# SCH_MEGO_Node_V1.net
KiCad netlist of a schematic drawn in Altium Designer
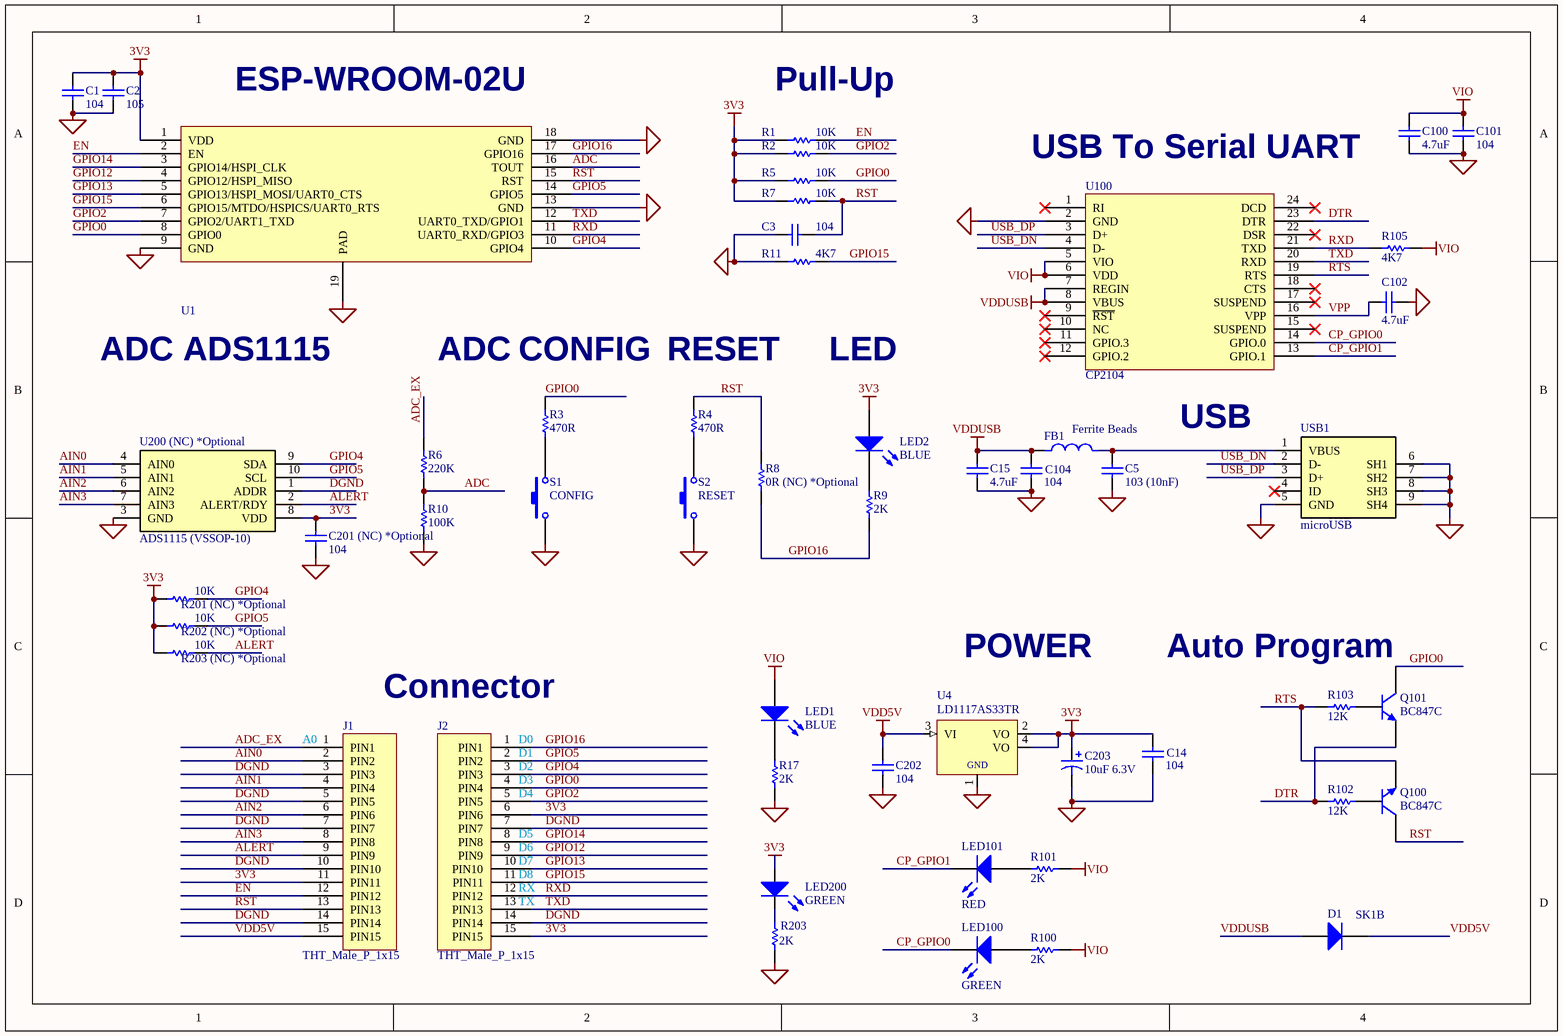
[diagram p0: SCH_MEGO_Node_V1.SchDoc]

(export (version "E")
  (design (tool "Eeschema 10.0.6"))
  (components
    (comp (ref "C1")
      (value "104")
      (footprint "IPC7351_EC_0603")
      (description "0.1µF ±5% 50V Ceramic Capacitor X7R 0603")
      (fields (field (name "MFG") "KEMET"))
      (libsource (lib "Miscellaneous Devices") (part "Cap Semi"))
    )
    (comp (ref "C2")
      (value "105")
      (footprint "IPC7351_EC_0603")
      (description "1µF ±5% 50V Ceramic Capacitor X7R 0603")
      (fields (field (name "MFG") "KEMET"))
      (libsource (lib "Miscellaneous Devices") (part "Cap Semi"))
    )
    (comp (ref "C3")
      (value "104")
      (footprint "IPC7351_EC_0603")
      (description "0.1µF ±5% 50V Ceramic Capacitor X7R 0603")
      (fields (field (name "MFG") "KEMET"))
      (libsource (lib "Miscellaneous Devices") (part "Cap Semi"))
    )
    (comp (ref "C5")
      (value "103 (10nF)")
      (footprint "IPC7351_EC_0603")
      (description "0.01µF ±5% 50V Ceramic Capacitor X7R 0603")
      (fields (field (name "MFG") "KEMET"))
      (libsource (lib "Miscellaneous Devices") (part "Cap Semi"))
    )
    (comp (ref "C14")
      (value "104")
      (footprint "IPC7351_EC_0603")
      (description "0.1µF ±5% 50V Ceramic Capacitor X7R 0603")
      (fields (field (name "MFG") "KEMET"))
      (libsource (lib "Miscellaneous Devices") (part "Cap Semi"))
    )
    (comp (ref "C15")
      (value "4.7uF")
      (footprint "IPC7351_EC_0603")
      (description "4.7µF ±10% 16V Ceramic Capacitor X5R 0805")
      (fields (field (name "MFG") "KEMET"))
      (libsource (lib "Miscellaneous Devices") (part "Cap"))
    )
    (comp (ref "C100")
      (value "4.7uF")
      (footprint "IPC7351_EC_0603")
      (description "4.7µF ±10% 16V Ceramic Capacitor X5R 0603")
      (fields (field (name "MFG") "KEMET"))
      (libsource (lib "Miscellaneous Devices") (part "Cap"))
    )
    (comp (ref "C101")
      (value "104")
      (footprint "IPC7351_EC_0603")
      (description "0.1µF ±5% 50V Ceramic Capacitor X7R 0603")
      (fields (field (name "MFG") "KEMET"))
      (libsource (lib "Miscellaneous Devices") (part "Cap Semi"))
    )
    (comp (ref "C102")
      (value "4.7uF")
      (footprint "IPC7351_EC_0603")
      (description "4.7µF ±10% 16V Ceramic Capacitor X5R 0603")
      (fields (field (name "MFG") "KEMET"))
      (libsource (lib "Miscellaneous Devices") (part "Cap"))
    )
    (comp (ref "C104")
      (value "104")
      (footprint "IPC7351_EC_0603")
      (description "0.1µF ±5% 50V Ceramic Capacitor X7R 0603")
      (fields (field (name "MFG") "KEMET"))
      (libsource (lib "Miscellaneous Devices") (part "Cap Semi"))
    )
    (comp (ref "C201 (NC) *Optional")
      (value "104")
      (footprint "IPC7351_EC_0603")
      (description "0.1µF ±5% 50V Ceramic Capacitor X7R 0603")
      (fields (field (name "MFG") "KEMET"))
      (libsource (lib "Miscellaneous Devices") (part "Cap Semi"))
    )
    (comp (ref "C202")
      (value "104")
      (footprint "IPC7351_EC_0603")
      (description "0.1µF ±5% 50V Ceramic Capacitor X7R 0603")
      (fields (field (name "MFG") "KEMET"))
      (libsource (lib "Miscellaneous Devices") (part "Cap Semi"))
    )
    (comp (ref "C203")
      (value "10uF 6.3V")
      (footprint "Tantalum_Capacitors:3216_18")
      (description "10µF 6.3V Tantalum Chip Capacitors ±20%")
      (fields (field (name "MFG") "ROHM"))
      (libsource (lib "Miscellaneous Devices") (part "Cap Pol1"))
    )
    (comp (ref "D1")
      (value "SK1B")
      (footprint "EDIS_SMA")
      (description "SK1B SCHOTTKY BARRIER DIODE 100V/1A")
      (fields (field (name "PART") "EDIS005") (field (name "PUBLISHER") "Altium Limited"))
      (libsource (lib "Miscellaneous Devices") (part "Diode"))
    )
    (comp (ref "FB1")
      (value "Ferrite Beads")
      (footprint "R0805")
      (description "Ferrite Beads Chip Beads 600Ω for Signal Line")
      (fields (field (name "MFG") "TDK"))
      (libsource (lib "RLC") (part "FB"))
    )
    (comp (ref "J1")
      (value "THT_Male_P_1x15")
      (footprint "HDR_1X15")
      (description "THT Male pin header strip 1x15")
      (libsource (lib "Vowstar_Connector") (part "THT_Male_P_1x15"))
    )
    (comp (ref "J2")
      (value "THT_Male_P_1x15")
      (footprint "HDR_1X15")
      (description "THT Male pin header strip 1x15")
      (libsource (lib "") (part "THT_Male_P_1x15_1"))
    )
    (comp (ref "LED1")
      (value "BLUE")
      (footprint "IPC7351_ELDS_0603")
      (description "LED RED 0603")
      (fields (field (name "MFG") "LITE-ON"))
      (libsource (lib "Miscellaneous Devices") (part "LED2"))
    )
    (comp (ref "LED2")
      (value "BLUE")
      (footprint "IPC7351_ELDS_0603")
      (description "LED RED 0603")
      (fields (field (name "MFG") "LITE-ON"))
      (libsource (lib "Miscellaneous Devices") (part "LED2"))
    )
    (comp (ref "LED100")
      (value "GREEN")
      (footprint "IPC7351_ELDS_0603")
      (description "LED BLUE 0603")
      (fields (field (name "MFG") "LITE-ON"))
      (libsource (lib "Miscellaneous Devices") (part "LED2"))
    )
    (comp (ref "LED101")
      (value "RED")
      (footprint "IPC7351_ELDS_0603")
      (description "LED RED 0603")
      (fields (field (name "MFG") "LITE-ON"))
      (libsource (lib "Miscellaneous Devices") (part "LED2"))
    )
    (comp (ref "LED200")
      (value "GREEN")
      (footprint "IPC7351_ELDS_0603")
      (description "LED BLUE 0603")
      (fields (field (name "MFG") "LITE-ON"))
      (libsource (lib "Miscellaneous Devices") (part "LED2"))
    )
    (comp (ref "Q100")
      (value "BC847C")
      (footprint "SOT-23-3")
      (description "Bipolar (BJT) Transistor NPN 45V 100mA 100MHz 250mW Surface Mount TO-236AB (SOT23)")
      (fields (field (name "MFG") "PHILIPS/NXP"))
      (libsource (lib "Miscellaneous Devices") (part "NPN"))
    )
    (comp (ref "Q101")
      (value "BC847C")
      (footprint "SOT-23-3")
      (description "Bipolar (BJT) Transistor NPN 45V 100mA 100MHz 250mW Surface Mount TO-236AB (SOT23)")
      (fields (field (name "MFG") "PHILIPS/NXP"))
      (libsource (lib "Miscellaneous Devices") (part "NPN"))
    )
    (comp (ref "R1")
      (value "10K")
      (footprint "IPC7351_ER_0603")
      (description "Resistor 0603")
      (libsource (lib "Miscellaneous Devices") (part "Res Semi"))
    )
    (comp (ref "R2")
      (value "10K")
      (footprint "IPC7351_ER_0603")
      (description "Resistor 0603")
      (libsource (lib "Miscellaneous Devices") (part "Res Semi"))
    )
    (comp (ref "R3")
      (value "470R")
      (footprint "IPC7351_ER_0603")
      (description "Resistor 0603")
      (libsource (lib "Miscellaneous Devices") (part "Res Semi"))
    )
    (comp (ref "R4")
      (value "470R")
      (footprint "IPC7351_ER_0603")
      (description "Resistor 0603")
      (libsource (lib "Miscellaneous Devices") (part "Res Semi"))
    )
    (comp (ref "R5")
      (value "10K")
      (footprint "IPC7351_ER_0603")
      (description "Resistor 0603")
      (libsource (lib "Miscellaneous Devices") (part "Res Semi"))
    )
    (comp (ref "R6")
      (value "220K")
      (footprint "IPC7351_ER_0603")
      (description "Resistor 0603 1%")
      (fields (field (name "MFG") "VISHAY"))
      (libsource (lib "Miscellaneous Devices") (part "Res Semi"))
    )
    (comp (ref "R7")
      (value "10K")
      (footprint "IPC7351_ER_0603")
      (description "Resistor 0603")
      (libsource (lib "Miscellaneous Devices") (part "Res Semi"))
    )
    (comp (ref "R8")
      (value "0R (NC) *Optional")
      (footprint "IPC7351_ER_0603")
      (description "Resistor 0603")
      (libsource (lib "Miscellaneous Devices") (part "Res Semi"))
    )
    (comp (ref "R9")
      (value "2K")
      (footprint "IPC7351_ER_0603")
      (description "Resistor 0603")
      (libsource (lib "Miscellaneous Devices") (part "Res Semi"))
    )
    (comp (ref "R10")
      (value "100K")
      (footprint "IPC7351_ER_0603")
      (description "Resistor 0603 1%")
      (fields (field (name "MFG") "ROHM"))
      (libsource (lib "Miscellaneous Devices") (part "Res Semi"))
    )
    (comp (ref "R11")
      (value "4K7")
      (footprint "IPC7351_ER_0603")
      (description "Resistor 0603")
      (libsource (lib "Miscellaneous Devices") (part "Res Semi"))
    )
    (comp (ref "R17")
      (value "2K")
      (footprint "IPC7351_ER_0603")
      (description "Resistor 0603")
      (libsource (lib "Miscellaneous Devices") (part "Res Semi"))
    )
    (comp (ref "R100")
      (value "2K")
      (footprint "IPC7351_ER_0603")
      (description "Resistor 0603")
      (libsource (lib "Miscellaneous Devices") (part "Res Semi"))
    )
    (comp (ref "R101")
      (value "2K")
      (footprint "IPC7351_ER_0603")
      (description "Resistor 0603")
      (libsource (lib "Miscellaneous Devices") (part "Res Semi"))
    )
    (comp (ref "R102")
      (value "12K")
      (footprint "IPC7351_ER_0603")
      (description "Resistor 0603")
      (libsource (lib "Miscellaneous Devices") (part "Res Semi"))
    )
    (comp (ref "R103")
      (value "12K")
      (footprint "IPC7351_ER_0603")
      (description "Resistor 0603")
      (libsource (lib "Miscellaneous Devices") (part "Res Semi"))
    )
    (comp (ref "R105")
      (value "4K7")
      (footprint "IPC7351_ER_0603")
      (description "Resistor 0603")
      (libsource (lib "Miscellaneous Devices") (part "Res Semi"))
    )
    (comp (ref "R201 (NC) *Optional")
      (value "10K")
      (footprint "IPC7351_ER_0603")
      (description "Resistor 0603")
      (libsource (lib "Miscellaneous Devices") (part "Res Semi"))
    )
    (comp (ref "R202 (NC) *Optional")
      (value "10K")
      (footprint "IPC7351_ER_0603")
      (description "Resistor 0603")
      (libsource (lib "Miscellaneous Devices") (part "Res Semi"))
    )
    (comp (ref "R203")
      (value "2K")
      (footprint "IPC7351_ER_0603")
      (description "Resistor 0603")
      (libsource (lib "Miscellaneous Devices") (part "Res Semi"))
    )
    (comp (ref "R203 (NC) *Optional")
      (value "10K")
      (footprint "IPC7351_ER_0603")
      (description "Resistor 0603")
      (libsource (lib "Miscellaneous Devices") (part "Res Semi"))
    )
    (comp (ref "S1")
      (value "CONFIG")
      (footprint "SKRKAEE010")
      (description "TACT SWITCH Size 6x6mm,2 Pins, SPST-NO")
      (fields (field (name "MFG") "WEALTH METAL"))
      (libsource (lib "Miscellaneous Devices") (part "SW-PB"))
    )
    (comp (ref "S2")
      (value "RESET")
      (footprint "SKRKAEE010")
      (description "TACT SWITCH Size 6x6mm,2 Pins, SPST-NO")
      (fields (field (name "MFG") "WEALTH METAL"))
      (libsource (lib "Miscellaneous Devices") (part "SW-PB"))
    )
    (comp (ref "U1")
      (value "ESP8266_WROOM_02U")
      (footprint "ESP-WROOM-02D")
      (description "WiFi Serial Transceiver Module (ESP8266) 02U-2MB")
      (fields (field (name "MFG") "ESPRESSIF"))
      (libsource (lib "MEGO_Node_V1") (part "ESP8266 WROOM 02"))
    )
    (comp (ref "U4")
      (value "LD1117AS33TR")
      (footprint "SOT-223-1")
      (description "LD1117AS33TR Positive Fixed Voltage Regulator LDO 3.3V/1A")
      (fields (field (name "MFG") "ST MICROELECTRONICS"))
      (libsource (lib "EspVIEW") (part "LM1117MPX-3.3"))
    )
    (comp (ref "U100")
      (value "CP2104")
      (footprint "QFN24")
      (description "USB Bridge, USB to UART USB 2.0 UART Interface 24QFN")
      (fields (field (name "MFG") "Silicon Labs"))
      (libsource (lib "nEWLibrary") (part "CP2104"))
    )
    (comp (ref "U200 (NC) *Optional")
      (value "ADS1115 (VSSOP-10)")
      (footprint "DGS-S-PDSO-G10")
      (description "ADS1115 Analog to Digital Converters - ADC 16B ADC w/ Int MUX PGA Comp Osc & Ref")
      (fields (field (name "MFG") "Texas Instruments"))
      (libsource (lib "ADS1115Schlib1") (part "ADS1115"))
    )
    (comp (ref "USB1")
      (value "microUSB")
      (footprint "MICRO-USB-CON")
      (libsource (lib "USB_PART_ALL") (part "microUSB"))
    )
  )
  (nets
    (net (code "1") (name "/ADC") (class "Default")
      (node (ref "R10") (pin "2") (pinfunction "2_2") (pintype "passive"))
      (node (ref "R6") (pin "2") (pinfunction "2_2") (pintype "passive"))
      (node (ref "U1") (pin "16") (pinfunction "TOUT_16") (pintype "passive"))
    )
    (net (code "2") (name "/ADC_EX") (class "Default")
      (node (ref "J1") (pin "1") (pinfunction "PIN1_1") (pintype "passive"))
      (node (ref "R6") (pin "1") (pinfunction "1_1") (pintype "passive"))
    )
    (net (code "3") (name "/AIN0") (class "Default")
      (node (ref "J1") (pin "2") (pinfunction "PIN2_2") (pintype "passive"))
      (node (ref "U200 (NC) *Optional") (pin "4") (pinfunction "AIN0_4") (pintype "passive"))
    )
    (net (code "4") (name "/AIN1") (class "Default")
      (node (ref "J1") (pin "4") (pinfunction "PIN4_4") (pintype "passive"))
      (node (ref "U200 (NC) *Optional") (pin "5") (pinfunction "AIN1_5") (pintype "passive"))
    )
    (net (code "5") (name "/AIN2") (class "Default")
      (node (ref "J1") (pin "6") (pinfunction "PIN6_6") (pintype "passive"))
      (node (ref "U200 (NC) *Optional") (pin "6") (pinfunction "AIN2_6") (pintype "passive"))
    )
    (net (code "6") (name "/AIN3") (class "Default")
      (node (ref "J1") (pin "8") (pinfunction "PIN8_8") (pintype "passive"))
      (node (ref "U200 (NC) *Optional") (pin "7") (pinfunction "AIN3_7") (pintype "passive"))
    )
    (net (code "7") (name "/ALERT") (class "Default")
      (node (ref "J1") (pin "9") (pinfunction "PIN9_9") (pintype "passive"))
      (node (ref "R203 (NC) *Optional") (pin "1") (pinfunction "1_1") (pintype "passive"))
      (node (ref "U200 (NC) *Optional") (pin "2") (pinfunction "ALERT/RDY_2") (pintype "passive"))
    )
    (net (code "8") (name "/CP_GPIO0") (class "Default")
      (node (ref "LED100") (pin "2") (pinfunction "K_2") (pintype "passive"))
      (node (ref "U100") (pin "14") (pinfunction "GPIO.0_14") (pintype "passive"))
    )
    (net (code "9") (name "/CP_GPIO1") (class "Default")
      (node (ref "LED101") (pin "2") (pinfunction "K_2") (pintype "passive"))
      (node (ref "U100") (pin "13") (pinfunction "GPIO.1_13") (pintype "passive"))
    )
    (net (code "10") (name "/DTR") (class "Default")
      (node (ref "Q101") (pin "2") (pinfunction "E_2") (pintype "passive"))
      (node (ref "R102") (pin "2") (pinfunction "2_2") (pintype "passive"))
      (node (ref "U100") (pin "23") (pinfunction "DTR_23") (pintype "passive"))
    )
    (net (code "11") (name "/EN") (class "Default")
      (node (ref "J1") (pin "12") (pinfunction "PIN12_12") (pintype "passive"))
      (node (ref "R1") (pin "1") (pinfunction "1_1") (pintype "passive"))
      (node (ref "U1") (pin "2") (pinfunction "EN_2") (pintype "passive"))
    )
    (net (code "12") (name "/GPIO0") (class "Default")
      (node (ref "J2") (pin "4") (pinfunction "PIN4_4") (pintype "passive"))
      (node (ref "Q101") (pin "3") (pinfunction "C_3") (pintype "passive"))
      (node (ref "R3") (pin "1") (pinfunction "1_1") (pintype "passive"))
      (node (ref "R5") (pin "1") (pinfunction "1_1") (pintype "passive"))
      (node (ref "U1") (pin "8") (pinfunction "GPIO0_8") (pintype "passive"))
    )
    (net (code "13") (name "/GPIO2") (class "Default")
      (node (ref "J2") (pin "5") (pinfunction "PIN5_5") (pintype "passive"))
      (node (ref "R2") (pin "1") (pinfunction "1_1") (pintype "passive"))
      (node (ref "U1") (pin "7") (pinfunction "GPIO2/UART1_TXD_7") (pintype "passive"))
    )
    (net (code "14") (name "/GPIO4") (class "Default")
      (node (ref "J2") (pin "3") (pinfunction "PIN3_3") (pintype "passive"))
      (node (ref "R201 (NC) *Optional") (pin "1") (pinfunction "1_1") (pintype "passive"))
      (node (ref "U1") (pin "10") (pinfunction "GPIO4_10") (pintype "passive"))
      (node (ref "U200 (NC) *Optional") (pin "9") (pinfunction "SDA_9") (pintype "passive"))
    )
    (net (code "15") (name "/GPIO5") (class "Default")
      (node (ref "J2") (pin "2") (pinfunction "PIN2_2") (pintype "passive"))
      (node (ref "R202 (NC) *Optional") (pin "1") (pinfunction "1_1") (pintype "passive"))
      (node (ref "U1") (pin "14") (pinfunction "GPIO5_14") (pintype "passive"))
      (node (ref "U200 (NC) *Optional") (pin "10") (pinfunction "SCL_10") (pintype "passive"))
    )
    (net (code "16") (name "/GPIO12") (class "Default")
      (node (ref "J2") (pin "9") (pinfunction "PIN9_9") (pintype "passive"))
      (node (ref "U1") (pin "4") (pinfunction "GPIO12/HSPI_MISO_4") (pintype "passive"))
    )
    (net (code "17") (name "/GPIO13") (class "Default")
      (node (ref "J2") (pin "10") (pinfunction "PIN10_10") (pintype "passive"))
      (node (ref "U1") (pin "5") (pinfunction "GPIO13/HSPI_MOSI/UART0_CTS_5") (pintype "passive"))
    )
    (net (code "18") (name "/GPIO14") (class "Default")
      (node (ref "J2") (pin "8") (pinfunction "PIN8_8") (pintype "passive"))
      (node (ref "U1") (pin "3") (pinfunction "GPIO14/HSPI_CLK_3") (pintype "passive"))
    )
    (net (code "19") (name "/GPIO15") (class "Default")
      (node (ref "J2") (pin "11") (pinfunction "PIN11_11") (pintype "passive"))
      (node (ref "R11") (pin "1") (pinfunction "1_1") (pintype "passive"))
      (node (ref "U1") (pin "6") (pinfunction "GPIO15/MTDO/HSPICS/UART0_RTS_6") (pintype "passive"))
    )
    (net (code "20") (name "/GPIO16") (class "Default")
      (node (ref "J2") (pin "1") (pinfunction "PIN1_1") (pintype "passive"))
      (node (ref "R8") (pin "1") (pinfunction "1_1") (pintype "passive"))
      (node (ref "R9") (pin "1") (pinfunction "1_1") (pintype "passive"))
      (node (ref "U1") (pin "17") (pinfunction "GPIO16_17") (pintype "passive"))
    )
    (net (code "21") (name "/RST") (class "Default")
      (node (ref "C3") (pin "2") (pinfunction "2_2") (pintype "passive"))
      (node (ref "J1") (pin "13") (pinfunction "PIN13_13") (pintype "passive"))
      (node (ref "Q100") (pin "3") (pinfunction "C_3") (pintype "passive"))
      (node (ref "R4") (pin "2") (pinfunction "2_2") (pintype "passive"))
      (node (ref "R7") (pin "1") (pinfunction "1_1") (pintype "passive"))
      (node (ref "R8") (pin "2") (pinfunction "2_2") (pintype "passive"))
      (node (ref "U1") (pin "15") (pinfunction "RST_15") (pintype "passive"))
    )
    (net (code "22") (name "/RTS") (class "Default")
      (node (ref "Q100") (pin "2") (pinfunction "E_2") (pintype "passive"))
      (node (ref "R103") (pin "2") (pinfunction "2_2") (pintype "passive"))
      (node (ref "U100") (pin "19") (pinfunction "RTS_19") (pintype "passive"))
    )
    (net (code "23") (name "/RXD") (class "Default")
      (node (ref "J2") (pin "12") (pinfunction "PIN12_12") (pintype "passive"))
      (node (ref "R105") (pin "1") (pinfunction "1_1") (pintype "passive"))
      (node (ref "U1") (pin "11") (pinfunction "UART0_RXD/GPIO3_11") (pintype "passive"))
      (node (ref "U100") (pin "21") (pinfunction "TXD_21") (pintype "passive"))
    )
    (net (code "24") (name "/TXD") (class "Default")
      (node (ref "J2") (pin "13") (pinfunction "PIN13_13") (pintype "passive"))
      (node (ref "U1") (pin "12") (pinfunction "UART0_TXD/GPIO1_12") (pintype "passive"))
      (node (ref "U100") (pin "20") (pinfunction "RXD_20") (pintype "passive"))
    )
    (net (code "25") (name "/USB_DN") (class "Default")
      (node (ref "U100") (pin "4") (pinfunction "D-_4") (pintype "passive"))
      (node (ref "USB1") (pin "2") (pinfunction "D-_2") (pintype "passive"))
    )
    (net (code "26") (name "/USB_DP") (class "Default")
      (node (ref "U100") (pin "3") (pinfunction "D+_3") (pintype "passive"))
      (node (ref "USB1") (pin "3") (pinfunction "D+_3") (pintype "passive"))
    )
    (net (code "27") (name "/VPP") (class "Default")
      (node (ref "C102") (pin "1") (pinfunction "1_1") (pintype "passive"))
      (node (ref "U100") (pin "16") (pinfunction "VPP_16") (pintype "passive"))
    )
    (net (code "28") (name "3V3") (class "Default")
      (node (ref "C1") (pin "2") (pinfunction "2_2") (pintype "passive"))
      (node (ref "C14") (pin "1") (pinfunction "1_1") (pintype "passive"))
      (node (ref "C2") (pin "2") (pinfunction "2_2") (pintype "passive"))
      (node (ref "C201 (NC) *Optional") (pin "2") (pinfunction "2_2") (pintype "passive"))
      (node (ref "C203") (pin "1") (pinfunction "1_1") (pintype "passive"))
      (node (ref "J1") (pin "11") (pinfunction "PIN11_11") (pintype "passive"))
      (node (ref "J2") (pin "15") (pinfunction "PIN15_15") (pintype "passive"))
      (node (ref "J2") (pin "6") (pinfunction "PIN6_6") (pintype "passive"))
      (node (ref "LED2") (pin "1") (pinfunction "A_1") (pintype "passive"))
      (node (ref "LED200") (pin "1") (pinfunction "A_1") (pintype "passive"))
      (node (ref "R1") (pin "2") (pinfunction "2_2") (pintype "passive"))
      (node (ref "R2") (pin "2") (pinfunction "2_2") (pintype "passive"))
      (node (ref "R201 (NC) *Optional") (pin "2") (pinfunction "2_2") (pintype "passive"))
      (node (ref "R202 (NC) *Optional") (pin "2") (pinfunction "2_2") (pintype "passive"))
      (node (ref "R203 (NC) *Optional") (pin "2") (pinfunction "2_2") (pintype "passive"))
      (node (ref "R5") (pin "2") (pinfunction "2_2") (pintype "passive"))
      (node (ref "R7") (pin "2") (pinfunction "2_2") (pintype "passive"))
      (node (ref "U1") (pin "1") (pinfunction "VDD_1") (pintype "passive"))
      (node (ref "U200 (NC) *Optional") (pin "8") (pinfunction "VDD_8") (pintype "passive"))
      (node (ref "U4") (pin "2") (pinfunction "VO_2") (pintype "passive"))
      (node (ref "U4") (pin "4") (pinfunction "VO_4") (pintype "passive"))
    )
    (net (code "29") (name "DGND") (class "Default")
      (node (ref "C1") (pin "1") (pinfunction "1_1") (pintype "passive"))
      (node (ref "C100") (pin "2") (pinfunction "2_2") (pintype "passive"))
      (node (ref "C101") (pin "2") (pinfunction "2_2") (pintype "passive"))
      (node (ref "C102") (pin "2") (pinfunction "2_2") (pintype "passive"))
      (node (ref "C104") (pin "2") (pinfunction "2_2") (pintype "passive"))
      (node (ref "C14") (pin "2") (pinfunction "2_2") (pintype "passive"))
      (node (ref "C15") (pin "2") (pinfunction "2_2") (pintype "passive"))
      (node (ref "C2") (pin "1") (pinfunction "1_1") (pintype "passive"))
      (node (ref "C201 (NC) *Optional") (pin "1") (pinfunction "1_1") (pintype "passive"))
      (node (ref "C202") (pin "1") (pinfunction "1_1") (pintype "passive"))
      (node (ref "C203") (pin "2") (pinfunction "2_2") (pintype "passive"))
      (node (ref "C3") (pin "1") (pinfunction "1_1") (pintype "passive"))
      (node (ref "C5") (pin "1") (pinfunction "1_1") (pintype "passive"))
      (node (ref "J1") (pin "10") (pinfunction "PIN10_10") (pintype "passive"))
      (node (ref "J1") (pin "14") (pinfunction "PIN14_14") (pintype "passive"))
      (node (ref "J1") (pin "3") (pinfunction "PIN3_3") (pintype "passive"))
      (node (ref "J1") (pin "5") (pinfunction "PIN5_5") (pintype "passive"))
      (node (ref "J1") (pin "7") (pinfunction "PIN7_7") (pintype "passive"))
      (node (ref "J2") (pin "14") (pinfunction "PIN14_14") (pintype "passive"))
      (node (ref "J2") (pin "7") (pinfunction "PIN7_7") (pintype "passive"))
      (node (ref "R10") (pin "1") (pinfunction "1_1") (pintype "passive"))
      (node (ref "R11") (pin "2") (pinfunction "2_2") (pintype "passive"))
      (node (ref "R17") (pin "1") (pinfunction "1_1") (pintype "passive"))
      (node (ref "R203") (pin "1") (pinfunction "1_1") (pintype "passive"))
      (node (ref "S1") (pin "2") (pinfunction "2_2") (pintype "passive"))
      (node (ref "S2") (pin "1") (pinfunction "1_1") (pintype "passive"))
      (node (ref "U1") (pin "13") (pinfunction "GND_13") (pintype "passive"))
      (node (ref "U1") (pin "18") (pinfunction "GND_18") (pintype "passive"))
      (node (ref "U1") (pin "19") (pinfunction "PAD_19") (pintype "passive"))
      (node (ref "U1") (pin "9") (pinfunction "GND_9") (pintype "passive"))
      (node (ref "U100") (pin "2") (pinfunction "GND_2") (pintype "passive"))
      (node (ref "U200 (NC) *Optional") (pin "1") (pinfunction "ADDR_1") (pintype "passive"))
      (node (ref "U200 (NC) *Optional") (pin "3") (pinfunction "GND_3") (pintype "passive"))
      (node (ref "U4") (pin "1") (pinfunction "GND_1") (pintype "passive"))
      (node (ref "USB1") (pin "5") (pinfunction "GND_5") (pintype "passive"))
      (node (ref "USB1") (pin "6") (pinfunction "SH1_6") (pintype "passive"))
      (node (ref "USB1") (pin "7") (pinfunction "SH2_7") (pintype "passive"))
      (node (ref "USB1") (pin "8") (pinfunction "SH3_8") (pintype "passive"))
      (node (ref "USB1") (pin "9") (pinfunction "SH4_9") (pintype "passive"))
    )
    (net (code "30") (name "Net-(LED1-K)") (class "Default")
      (node (ref "LED1") (pin "2") (pinfunction "K_2") (pintype "passive"))
      (node (ref "R17") (pin "2") (pinfunction "2_2") (pintype "passive"))
    )
    (net (code "31") (name "Net-(LED2-K)") (class "Default")
      (node (ref "LED2") (pin "2") (pinfunction "K_2") (pintype "passive"))
      (node (ref "R9") (pin "2") (pinfunction "2_2") (pintype "passive"))
    )
    (net (code "32") (name "Net-(LED100-A)") (class "Default")
      (node (ref "LED100") (pin "1") (pinfunction "A_1") (pintype "passive"))
      (node (ref "R100") (pin "1") (pinfunction "1_1") (pintype "passive"))
    )
    (net (code "33") (name "Net-(LED101-A)") (class "Default")
      (node (ref "LED101") (pin "1") (pinfunction "A_1") (pintype "passive"))
      (node (ref "R101") (pin "1") (pinfunction "1_1") (pintype "passive"))
    )
    (net (code "34") (name "Net-(LED200-K)") (class "Default")
      (node (ref "LED200") (pin "2") (pinfunction "K_2") (pintype "passive"))
      (node (ref "R203") (pin "2") (pinfunction "2_2") (pintype "passive"))
    )
    (net (code "35") (name "Net-(Q100-B)") (class "Default")
      (node (ref "Q100") (pin "1") (pinfunction "B_1") (pintype "passive"))
      (node (ref "R102") (pin "1") (pinfunction "1_1") (pintype "passive"))
    )
    (net (code "36") (name "Net-(Q101-B)") (class "Default")
      (node (ref "Q101") (pin "1") (pinfunction "B_1") (pintype "passive"))
      (node (ref "R103") (pin "1") (pinfunction "1_1") (pintype "passive"))
    )
    (net (code "37") (name "Net-(R3-Pad2)") (class "Default")
      (node (ref "R3") (pin "2") (pinfunction "2_2") (pintype "passive"))
      (node (ref "S1") (pin "1") (pinfunction "1_1") (pintype "passive"))
    )
    (net (code "38") (name "Net-(R4-Pad1)") (class "Default")
      (node (ref "R4") (pin "1") (pinfunction "1_1") (pintype "passive"))
      (node (ref "S2") (pin "2") (pinfunction "2_2") (pintype "passive"))
    )
    (net (code "39") (name "Net-(USB1-VBUS)") (class "Default")
      (node (ref "C5") (pin "2") (pinfunction "2_2") (pintype "passive"))
      (node (ref "FB1") (pin "2") (pinfunction "2_2") (pintype "passive"))
      (node (ref "USB1") (pin "1") (pinfunction "VBUS_1") (pintype "passive"))
    )
    (net (code "40") (name "VDD5V") (class "Default")
      (node (ref "C202") (pin "2") (pinfunction "2_2") (pintype "passive"))
      (node (ref "D1") (pin "2") (pinfunction "K_2") (pintype "passive"))
      (node (ref "J1") (pin "15") (pinfunction "PIN15_15") (pintype "passive"))
      (node (ref "U4") (pin "3") (pinfunction "VI_3") (pintype "input"))
    )
    (net (code "41") (name "VDDUSB") (class "Default")
      (node (ref "C104") (pin "1") (pinfunction "1_1") (pintype "passive"))
      (node (ref "C15") (pin "1") (pinfunction "1_1") (pintype "passive"))
      (node (ref "D1") (pin "1") (pinfunction "A_1") (pintype "passive"))
      (node (ref "FB1") (pin "1") (pinfunction "1_1") (pintype "passive"))
      (node (ref "U100") (pin "7") (pinfunction "REGIN_7") (pintype "passive"))
      (node (ref "U100") (pin "8") (pinfunction "VBUS_8") (pintype "passive"))
    )
    (net (code "42") (name "VIO") (class "Default")
      (node (ref "C100") (pin "1") (pinfunction "1_1") (pintype "passive"))
      (node (ref "C101") (pin "1") (pinfunction "1_1") (pintype "passive"))
      (node (ref "LED1") (pin "1") (pinfunction "A_1") (pintype "passive"))
      (node (ref "R100") (pin "2") (pinfunction "2_2") (pintype "passive"))
      (node (ref "R101") (pin "2") (pinfunction "2_2") (pintype "passive"))
      (node (ref "R105") (pin "2") (pinfunction "2_2") (pintype "passive"))
      (node (ref "U100") (pin "5") (pinfunction "VIO_5") (pintype "passive"))
      (node (ref "U100") (pin "6") (pinfunction "VDD_6") (pintype "passive"))
    )
    (net (code "43") (name "unconnected-(U100-CTS-Pad18)") (class "Default")
      (node (ref "U100") (pin "18") (pinfunction "CTS_18") (pintype "passive+no_connect"))
    )
    (net (code "44") (name "unconnected-(U100-DCD-Pad24)") (class "Default")
      (node (ref "U100") (pin "24") (pinfunction "DCD_24") (pintype "passive+no_connect"))
    )
    (net (code "45") (name "unconnected-(U100-DSR-Pad22)") (class "Default")
      (node (ref "U100") (pin "22") (pinfunction "DSR_22") (pintype "passive+no_connect"))
    )
    (net (code "46") (name "unconnected-(U100-GPIO.2-Pad12)") (class "Default")
      (node (ref "U100") (pin "12") (pinfunction "GPIO.2_12") (pintype "passive+no_connect"))
    )
    (net (code "47") (name "unconnected-(U100-GPIO.3-Pad11)") (class "Default")
      (node (ref "U100") (pin "11") (pinfunction "GPIO.3_11") (pintype "passive+no_connect"))
    )
    (net (code "48") (name "unconnected-(U100-NC-Pad10)") (class "Default")
      (node (ref "U100") (pin "10") (pinfunction "NC_10") (pintype "passive+no_connect"))
    )
    (net (code "49") (name "unconnected-(U100-RI-Pad1)") (class "Default")
      (node (ref "U100") (pin "1") (pinfunction "RI_1") (pintype "passive+no_connect"))
    )
    (net (code "50") (name "unconnected-(U100-SUSPEND-Pad15)") (class "Default")
      (node (ref "U100") (pin "15") (pinfunction "SUSPEND_15") (pintype "passive+no_connect"))
    )
    (net (code "51") (name "unconnected-(U100-SUSPEND-Pad17)") (class "Default")
      (node (ref "U100") (pin "17") (pinfunction "SUSPEND_17") (pintype "passive+no_connect"))
    )
    (net (code "52") (name "unconnected-(U100-~{RST}-Pad9)") (class "Default")
      (node (ref "U100") (pin "9") (pinfunction "~{RST}_9") (pintype "passive+no_connect"))
    )
    (net (code "53") (name "unconnected-(USB1-ID-Pad4)") (class "Default")
      (node (ref "USB1") (pin "4") (pinfunction "ID_4") (pintype "passive+no_connect"))
    )
  )
)
